# MCP2551.net
KiCad netlist of a schematic drawn in Altium Designer
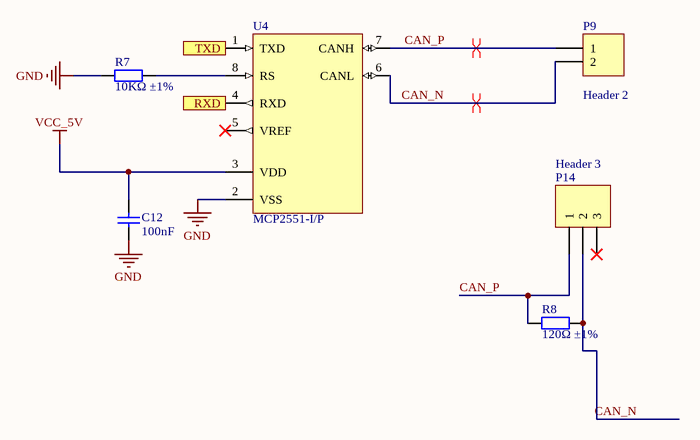
[diagram p0: MCP2551.SchDoc]

(export (version "E")
  (design (tool "Eeschema 10.0.6"))
  (components
    (comp (ref "C12")
      (value "100nF")
      (footprint "0603_C")
      (description "Chip capacitors")
      (fields (field (name "MANUFACTURER") "YAGEO") (field (name "PARTNUMBER") "CC0603KRX7R9BB104"))
      (libsource (lib "Cap") (part "0603 100nF (104) 10% 50V"))
    )
    (comp (ref "P9")
      (value "Header 2")
      (footprint "HDR1X2")
      (description "Header, 2-Pin")
      (fields (field (name "PUBLISHER") "Altium Limited"))
      (libsource (lib "Miscellaneous Connectors") (part "Header 2"))
    )
    (comp (ref "P14")
      (value "Header 3")
      (footprint "HDR1X3")
      (description "Header, 3-Pin")
      (fields (field (name "PUBLISHER") "Altium Limited"))
      (libsource (lib "Miscellaneous Connectors") (part "Header 3"))
    )
    (comp (ref "R7")
      (value "10KΩ ±1%")
      (footprint "0805_R")
      (description "Chip resistor")
      (fields (field (name "MANUFACTURER") "Uniroyal Elec") (field (name "PARTNUMBER") "0805W8F1002T5E"))
      (libsource (lib "RES") (part "0805 10K (1002) 1%"))
    )
    (comp (ref "R8")
      (value "120Ω ±1%")
      (footprint "0603_R")
      (description "Chip resistor")
      (fields (field (name "MANUFACTURER") "Uniroyal Elec") (field (name "PARTNUMBER") "0603WAF1200T5E"))
      (libsource (lib "RES") (part "0603 120R (1200) 1%"))
    )
    (comp (ref "U4")
      (value "MCP2551-I/P")
      (footprint "PDIP300-P8")
      (description "High-Speed CAN Transceiver, 8-Pin PDIP, Industrial Temperature")
      (libsource (lib "Altium Content Vault") (part "COM-TRX-MCP2551-8"))
    )
  )
  (nets
    (net (code "1") (name "/CAN_N") (class "Default")
      (node (ref "P14") (pin "2") (pinfunction "2_2") (pintype "passive"))
      (node (ref "P9") (pin "2") (pinfunction "2_2") (pintype "passive"))
      (node (ref "R8") (pin "1") (pinfunction "1_1") (pintype "passive"))
      (node (ref "U4") (pin "6") (pinfunction "CANL_6") (pintype "bidirectional"))
    )
    (net (code "2") (name "/CAN_P") (class "Default")
      (node (ref "P14") (pin "1") (pinfunction "1_1") (pintype "passive"))
      (node (ref "P9") (pin "1") (pinfunction "1_1") (pintype "passive"))
      (node (ref "R8") (pin "2") (pinfunction "2_2") (pintype "passive"))
      (node (ref "U4") (pin "7") (pinfunction "CANH_7") (pintype "bidirectional"))
    )
    (net (code "3") (name "/RXD") (class "Default")
      (node (ref "U4") (pin "4") (pinfunction "RXD_4") (pintype "output"))
    )
    (net (code "4") (name "/TXD") (class "Default")
      (node (ref "U4") (pin "1") (pinfunction "TXD_1") (pintype "input"))
    )
    (net (code "5") (name "GND") (class "Default")
      (node (ref "C12") (pin "1") (pinfunction "1_1") (pintype "passive"))
      (node (ref "R7") (pin "2") (pinfunction "2_2") (pintype "passive"))
      (node (ref "U4") (pin "2") (pinfunction "VSS_2") (pintype "power_in"))
    )
    (net (code "6") (name "Net-(U4-RS)") (class "Default")
      (node (ref "R7") (pin "1") (pinfunction "1_1") (pintype "passive"))
      (node (ref "U4") (pin "8") (pinfunction "RS_8") (pintype "input"))
    )
    (net (code "7") (name "VCC_5V") (class "Default")
      (node (ref "C12") (pin "2") (pinfunction "2_2") (pintype "passive"))
      (node (ref "U4") (pin "3") (pinfunction "VDD_3") (pintype "power_in"))
    )
    (net (code "8") (name "unconnected-(P14-Pad3)") (class "Default")
      (node (ref "P14") (pin "3") (pinfunction "3_3") (pintype "passive+no_connect"))
    )
    (net (code "9") (name "unconnected-(U4-VREF-Pad5)") (class "Default")
      (node (ref "U4") (pin "5") (pinfunction "VREF_5") (pintype "output+no_connect"))
    )
  )
)
